# DC_Motor_Controller_with_SLAVE_OUT.net
KiCad netlist of a schematic drawn in EAGLE
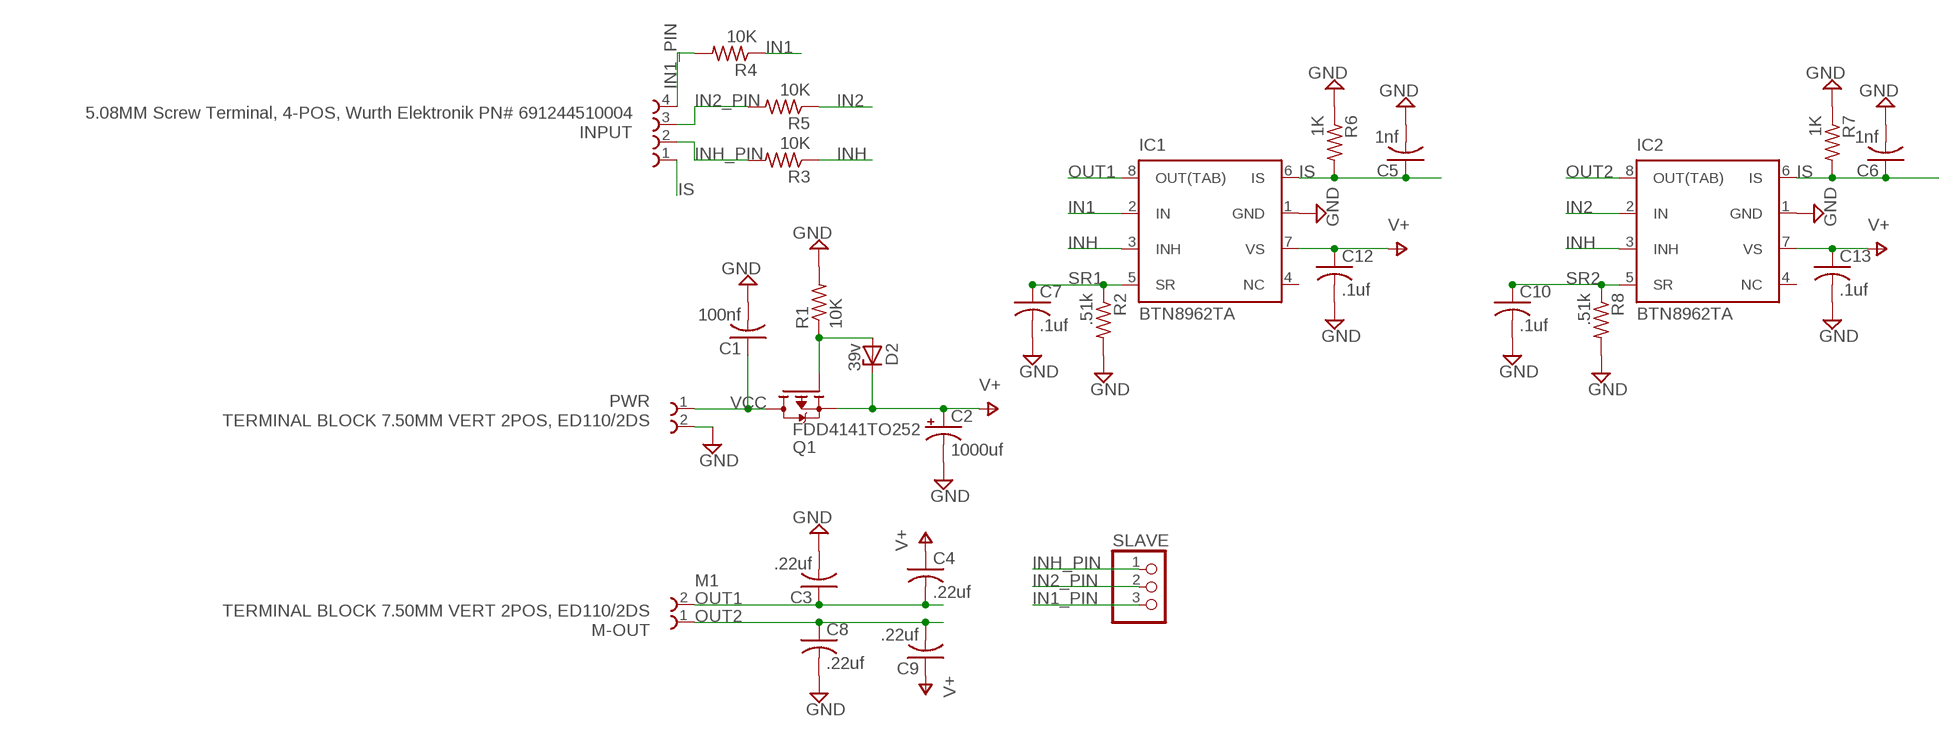
[diagram p0: schematic, sheet 1]

(export (version "E")
  (design (tool "Eeschema 10.0.6"))
  (components
    (comp (ref "C1")
      (value "100nf")
      (footprint "eagle-import:C0805")
      (libsource (lib "eagle-import") (part "C-USC0805"))
    )
    (comp (ref "C2")
      (value "1000uf")
      (footprint "eagle-import:TT5D10")
      (libsource (lib "eagle-import") (part "CPOL-USTT5D10"))
    )
    (comp (ref "C3")
      (value ".22uf")
      (footprint "eagle-import:C0805")
      (libsource (lib "eagle-import") (part "C-USC0805"))
    )
    (comp (ref "C4")
      (value ".22uf")
      (footprint "eagle-import:C0805")
      (libsource (lib "eagle-import") (part "C-USC0805"))
    )
    (comp (ref "C5")
      (value "1nf")
      (footprint "eagle-import:C0805")
      (libsource (lib "eagle-import") (part "C-USC0805"))
    )
    (comp (ref "C6")
      (value "1nf")
      (footprint "eagle-import:C0805")
      (libsource (lib "eagle-import") (part "C-USC0805"))
    )
    (comp (ref "C7")
      (value ".1uf")
      (footprint "eagle-import:C0805")
      (libsource (lib "eagle-import") (part "C-USC0805"))
    )
    (comp (ref "C8")
      (value ".22uf")
      (footprint "eagle-import:C0805")
      (libsource (lib "eagle-import") (part "C-USC0805"))
    )
    (comp (ref "C9")
      (value ".22uf")
      (footprint "eagle-import:C0805")
      (libsource (lib "eagle-import") (part "C-USC0805"))
    )
    (comp (ref "C10")
      (value ".1uf")
      (footprint "eagle-import:C0805")
      (libsource (lib "eagle-import") (part "C-USC0805"))
    )
    (comp (ref "C12")
      (value ".1uf")
      (footprint "eagle-import:C0805")
      (libsource (lib "eagle-import") (part "C-USC0805"))
    )
    (comp (ref "C13")
      (value ".1uf")
      (footprint "eagle-import:C0805")
      (libsource (lib "eagle-import") (part "C-USC0805"))
    )
    (comp (ref "D2")
      (value "39v")
      (footprint "eagle-import:SMB")
      (libsource (lib "eagle-import") (part "ZENER-DIODESMB"))
    )
    (comp (ref "IC1")
      (value "BTN8962TA")
      (footprint "eagle-import:P-TO263-7-1_LG_PADS")
      (libsource (lib "eagle-import") (part "BTN8962TA"))
    )
    (comp (ref "IC2")
      (value "BTN8962TA")
      (footprint "eagle-import:P-TO263-7-1_LG_PADS")
      (libsource (lib "eagle-import") (part "BTN8962TA"))
    )
    (comp (ref "INPUT")
      (value "5.08MM Screw Terminal, 4-POS, Wurth Elektronik PN# 691244510004")
      (footprint "eagle-import:691244510004")
      (libsource (lib "eagle-import") (part "691244510004"))
    )
    (comp (ref "M-OUT")
      (value "TERMINAL BLOCK 7.50MM VERT 2POS, ED110/2DS")
      (footprint "eagle-import:7-5MM-SCREW-TERM")
      (libsource (lib "eagle-import") (part "7-5MM-SCREW-TERM"))
    )
    (comp (ref "PWR")
      (value "TERMINAL BLOCK 7.50MM VERT 2POS, ED110/2DS")
      (footprint "eagle-import:7-5MM-SCREW-TERM")
      (libsource (lib "eagle-import") (part "7-5MM-SCREW-TERM"))
    )
    (comp (ref "Q1")
      (value "FDD4141TO252")
      (footprint "eagle-import:TO252")
      (libsource (lib "eagle-import") (part "FDD4141TO252"))
    )
    (comp (ref "R1")
      (value "10K")
      (footprint "eagle-import:R0805")
      (libsource (lib "eagle-import") (part "R-US_R0805"))
    )
    (comp (ref "R2")
      (value ".51k")
      (footprint "eagle-import:R0805")
      (libsource (lib "eagle-import") (part "R-US_R0805"))
    )
    (comp (ref "R3")
      (value "10K")
      (footprint "eagle-import:R0805")
      (libsource (lib "eagle-import") (part "R-US_R0805"))
    )
    (comp (ref "R4")
      (value "10K")
      (footprint "eagle-import:R0805")
      (libsource (lib "eagle-import") (part "R-US_R0805"))
    )
    (comp (ref "R5")
      (value "10K")
      (footprint "eagle-import:R0805")
      (libsource (lib "eagle-import") (part "R-US_R0805"))
    )
    (comp (ref "R6")
      (value "1K")
      (footprint "eagle-import:R0805")
      (libsource (lib "eagle-import") (part "R-US_R0805"))
    )
    (comp (ref "R7")
      (value "1K")
      (footprint "eagle-import:R0805")
      (libsource (lib "eagle-import") (part "R-US_R0805"))
    )
    (comp (ref "R8")
      (value ".51k")
      (footprint "eagle-import:R0805")
      (libsource (lib "eagle-import") (part "R-US_R0805"))
    )
    (comp (ref "SLAVE")
      (value "PINHD-1X3CB")
      (footprint "eagle-import:1X03-CLEANBIG")
      (libsource (lib "eagle-import") (part "PINHD-1X3CB"))
    )
  )
  (nets
    (net (code "1") (name "/IN1") (class "Default")
      (node (ref "IC1") (pin "2") (pinfunction "IN_2") (pintype "input"))
      (node (ref "R4") (pin "1") (pinfunction "1_1") (pintype "passive"))
    )
    (net (code "2") (name "/IN1_PIN") (class "Default")
      (node (ref "INPUT") (pin "4") (pinfunction "4_4") (pintype "passive"))
      (node (ref "R4") (pin "2") (pinfunction "2_2") (pintype "passive"))
      (node (ref "SLAVE") (pin "3") (pinfunction "3_3") (pintype "passive"))
    )
    (net (code "3") (name "/IN2") (class "Default")
      (node (ref "IC2") (pin "2") (pinfunction "IN_2") (pintype "input"))
      (node (ref "R5") (pin "1") (pinfunction "1_1") (pintype "passive"))
    )
    (net (code "4") (name "/IN2_PIN") (class "Default")
      (node (ref "INPUT") (pin "3") (pinfunction "3_3") (pintype "passive"))
      (node (ref "R5") (pin "2") (pinfunction "2_2") (pintype "passive"))
      (node (ref "SLAVE") (pin "2") (pinfunction "2_2") (pintype "passive"))
    )
    (net (code "5") (name "/INH") (class "Default")
      (node (ref "IC1") (pin "3") (pinfunction "INH_3") (pintype "input"))
      (node (ref "IC2") (pin "3") (pinfunction "INH_3") (pintype "input"))
      (node (ref "R3") (pin "1") (pinfunction "1_1") (pintype "passive"))
    )
    (net (code "6") (name "/INH_PIN") (class "Default")
      (node (ref "INPUT") (pin "2") (pinfunction "2_2") (pintype "passive"))
      (node (ref "R3") (pin "2") (pinfunction "2_2") (pintype "passive"))
      (node (ref "SLAVE") (pin "1") (pinfunction "1_1") (pintype "passive"))
    )
    (net (code "7") (name "/IS") (class "Default")
      (node (ref "C5") (pin "1") (pinfunction "1_1") (pintype "passive"))
      (node (ref "C6") (pin "1") (pinfunction "1_1") (pintype "passive"))
      (node (ref "IC1") (pin "6") (pinfunction "IS_6") (pintype "output"))
      (node (ref "IC2") (pin "6") (pinfunction "IS_6") (pintype "output"))
      (node (ref "INPUT") (pin "1") (pinfunction "1_1") (pintype "passive"))
      (node (ref "R6") (pin "2") (pinfunction "2_2") (pintype "passive"))
      (node (ref "R7") (pin "2") (pinfunction "2_2") (pintype "passive"))
    )
    (net (code "8") (name "/OUT1") (class "Default")
      (node (ref "C3") (pin "1") (pinfunction "1_1") (pintype "passive"))
      (node (ref "C4") (pin "2") (pinfunction "2_2") (pintype "passive"))
      (node (ref "IC1") (pin "8") (pinfunction "OUT(TAB)_8") (pintype "output"))
      (node (ref "M-OUT") (pin "2") (pinfunction "2_2") (pintype "passive"))
    )
    (net (code "9") (name "/OUT2") (class "Default")
      (node (ref "C8") (pin "1") (pinfunction "1_1") (pintype "passive"))
      (node (ref "C9") (pin "2") (pinfunction "2_2") (pintype "passive"))
      (node (ref "IC2") (pin "8") (pinfunction "OUT(TAB)_8") (pintype "output"))
      (node (ref "M-OUT") (pin "1") (pinfunction "1_1") (pintype "passive"))
    )
    (net (code "10") (name "/SR1") (class "Default")
      (node (ref "C7") (pin "1") (pinfunction "1_1") (pintype "passive"))
      (node (ref "IC1") (pin "5") (pinfunction "SR_5") (pintype "input"))
      (node (ref "R2") (pin "1") (pinfunction "1_1") (pintype "passive"))
    )
    (net (code "11") (name "/SR2") (class "Default")
      (node (ref "C10") (pin "1") (pinfunction "1_1") (pintype "passive"))
      (node (ref "IC2") (pin "5") (pinfunction "SR_5") (pintype "input"))
      (node (ref "R8") (pin "1") (pinfunction "1_1") (pintype "passive"))
    )
    (net (code "12") (name "/VCC") (class "Default")
      (node (ref "C1") (pin "1") (pinfunction "1_1") (pintype "passive"))
      (node (ref "PWR") (pin "1") (pinfunction "1_1") (pintype "passive"))
      (node (ref "Q1") (pin "3") (pinfunction "D_3") (pintype "passive"))
    )
    (net (code "13") (name "GND") (class "Default")
      (node (ref "C1") (pin "2") (pinfunction "2_2") (pintype "passive"))
      (node (ref "C10") (pin "2") (pinfunction "2_2") (pintype "passive"))
      (node (ref "C12") (pin "2") (pinfunction "2_2") (pintype "passive"))
      (node (ref "C13") (pin "2") (pinfunction "2_2") (pintype "passive"))
      (node (ref "C2") (pin "-") (pinfunction "-_-") (pintype "passive"))
      (node (ref "C3") (pin "2") (pinfunction "2_2") (pintype "passive"))
      (node (ref "C5") (pin "2") (pinfunction "2_2") (pintype "passive"))
      (node (ref "C6") (pin "2") (pinfunction "2_2") (pintype "passive"))
      (node (ref "C7") (pin "2") (pinfunction "2_2") (pintype "passive"))
      (node (ref "C8") (pin "2") (pinfunction "2_2") (pintype "passive"))
      (node (ref "IC1") (pin "1") (pinfunction "GND_1") (pintype "power_in"))
      (node (ref "IC2") (pin "1") (pinfunction "GND_1") (pintype "power_in"))
      (node (ref "PWR") (pin "2") (pinfunction "2_2") (pintype "passive"))
      (node (ref "R1") (pin "2") (pinfunction "2_2") (pintype "passive"))
      (node (ref "R2") (pin "2") (pinfunction "2_2") (pintype "passive"))
      (node (ref "R6") (pin "1") (pinfunction "1_1") (pintype "passive"))
      (node (ref "R7") (pin "1") (pinfunction "1_1") (pintype "passive"))
      (node (ref "R8") (pin "2") (pinfunction "2_2") (pintype "passive"))
    )
    (net (code "14") (name "Net-(Q1-G)") (class "Default")
      (node (ref "D2") (pin "A") (pinfunction "A_A") (pintype "passive"))
      (node (ref "Q1") (pin "1") (pinfunction "G_1") (pintype "passive"))
      (node (ref "R1") (pin "1") (pinfunction "1_1") (pintype "passive"))
    )
    (net (code "15") (name "V+") (class "Default")
      (node (ref "C12") (pin "1") (pinfunction "1_1") (pintype "passive"))
      (node (ref "C13") (pin "1") (pinfunction "1_1") (pintype "passive"))
      (node (ref "C2") (pin "+") (pinfunction "+_+") (pintype "passive"))
      (node (ref "C4") (pin "1") (pinfunction "1_1") (pintype "passive"))
      (node (ref "C9") (pin "1") (pinfunction "1_1") (pintype "passive"))
      (node (ref "D2") (pin "C") (pinfunction "C_C") (pintype "passive"))
      (node (ref "IC1") (pin "7") (pinfunction "VS_7") (pintype "power_in"))
      (node (ref "IC2") (pin "7") (pinfunction "VS_7") (pintype "power_in"))
      (node (ref "Q1") (pin "2") (pinfunction "S_2") (pintype "passive"))
    )
    (net (code "16") (name "unconnected-(IC1-NC-Pad4)") (class "Default")
      (node (ref "IC1") (pin "4") (pinfunction "NC_4") (pintype "no_connect"))
    )
    (net (code "17") (name "unconnected-(IC2-NC-Pad4)") (class "Default")
      (node (ref "IC2") (pin "4") (pinfunction "NC_4") (pintype "no_connect"))
    )
  )
)
